# StepDrive.net
KiCad netlist of a schematic drawn in Altium Designer
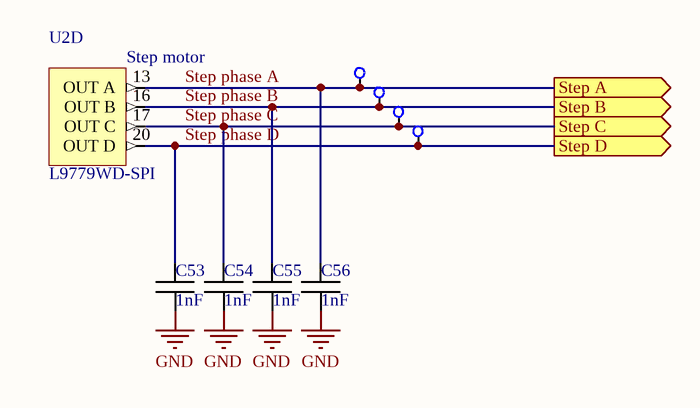
[diagram p0: StepDrive.SchDoc]

(export (version "E")
  (design (tool "Eeschema 10.0.6"))
  (components
    (comp (ref "C53")
      (value "1nF")
      (footprint "SMD 0603")
      (description "CC0603KRX7R9BB102")
      (libsource (lib "Maks_lib") (part "Capasitor"))
    )
    (comp (ref "C54")
      (value "1nF")
      (footprint "SMD 0603")
      (description "CC0603KRX7R9BB102")
      (libsource (lib "Maks_lib") (part "Capasitor"))
    )
    (comp (ref "C55")
      (value "1nF")
      (footprint "SMD 0603")
      (description "CC0603KRX7R9BB102")
      (libsource (lib "Maks_lib") (part "Capasitor"))
    )
    (comp (ref "C56")
      (value "1nF")
      (footprint "SMD 0603")
      (description "CC0603KRX7R9BB102")
      (libsource (lib "Maks_lib") (part "Capasitor"))
    )
    (comp (ref "TP34")
      (value "TestPoint")
      (footprint "TESTPOINT")
      (description "testPoint")
      (libsource (lib "Maks_lib") (part "TestPoint"))
    )
    (comp (ref "TP35")
      (value "TestPoint")
      (footprint "TESTPOINT")
      (description "testPoint")
      (libsource (lib "Maks_lib") (part "TestPoint"))
    )
    (comp (ref "TP36")
      (value "TestPoint")
      (footprint "TESTPOINT")
      (description "testPoint")
      (libsource (lib "Maks_lib") (part "TestPoint"))
    )
    (comp (ref "TP37")
      (value "TestPoint")
      (footprint "TESTPOINT")
      (description "testPoint")
      (libsource (lib "Maks_lib") (part "TestPoint"))
    )
    (comp (ref "U2")
      (value "L9779WD-SPI")
      (footprint "HiQUAD-64")
      (description "Multifunction IC for engine management system")
      (libsource (lib "Maks_lib") (part "L9779WD-SPI"))
    )
  )
  (nets
    (net (code "1") (name "/Step phase A") (class "Default")
      (node (ref "C56") (pin "2") (pinfunction "2_2") (pintype "passive"))
      (node (ref "TP34") (pin "0") (pinfunction "0_0") (pintype "passive"))
      (node (ref "U2") (pin "13") (pinfunction "OUT_A_13") (pintype "output"))
    )
    (net (code "2") (name "/Step phase B") (class "Default")
      (node (ref "C55") (pin "2") (pinfunction "2_2") (pintype "passive"))
      (node (ref "TP35") (pin "0") (pinfunction "0_0") (pintype "passive"))
      (node (ref "U2") (pin "16") (pinfunction "OUT_B_16") (pintype "output"))
    )
    (net (code "3") (name "/Step phase C") (class "Default")
      (node (ref "C54") (pin "2") (pinfunction "2_2") (pintype "passive"))
      (node (ref "TP36") (pin "0") (pinfunction "0_0") (pintype "passive"))
      (node (ref "U2") (pin "17") (pinfunction "OUT_C_17") (pintype "output"))
    )
    (net (code "4") (name "/Step phase D") (class "Default")
      (node (ref "C53") (pin "2") (pinfunction "2_2") (pintype "passive"))
      (node (ref "TP37") (pin "0") (pinfunction "0_0") (pintype "passive"))
      (node (ref "U2") (pin "20") (pinfunction "OUT_D_20") (pintype "output"))
    )
    (net (code "5") (name "GND") (class "Default")
      (node (ref "C53") (pin "1") (pinfunction "1_1") (pintype "passive"))
      (node (ref "C54") (pin "1") (pinfunction "1_1") (pintype "passive"))
      (node (ref "C55") (pin "1") (pinfunction "1_1") (pintype "passive"))
      (node (ref "C56") (pin "1") (pinfunction "1_1") (pintype "passive"))
    )
  )
)
